# SmartHomePLC_Licenta_V2sch.net
KiCad netlist of a schematic drawn in EAGLE
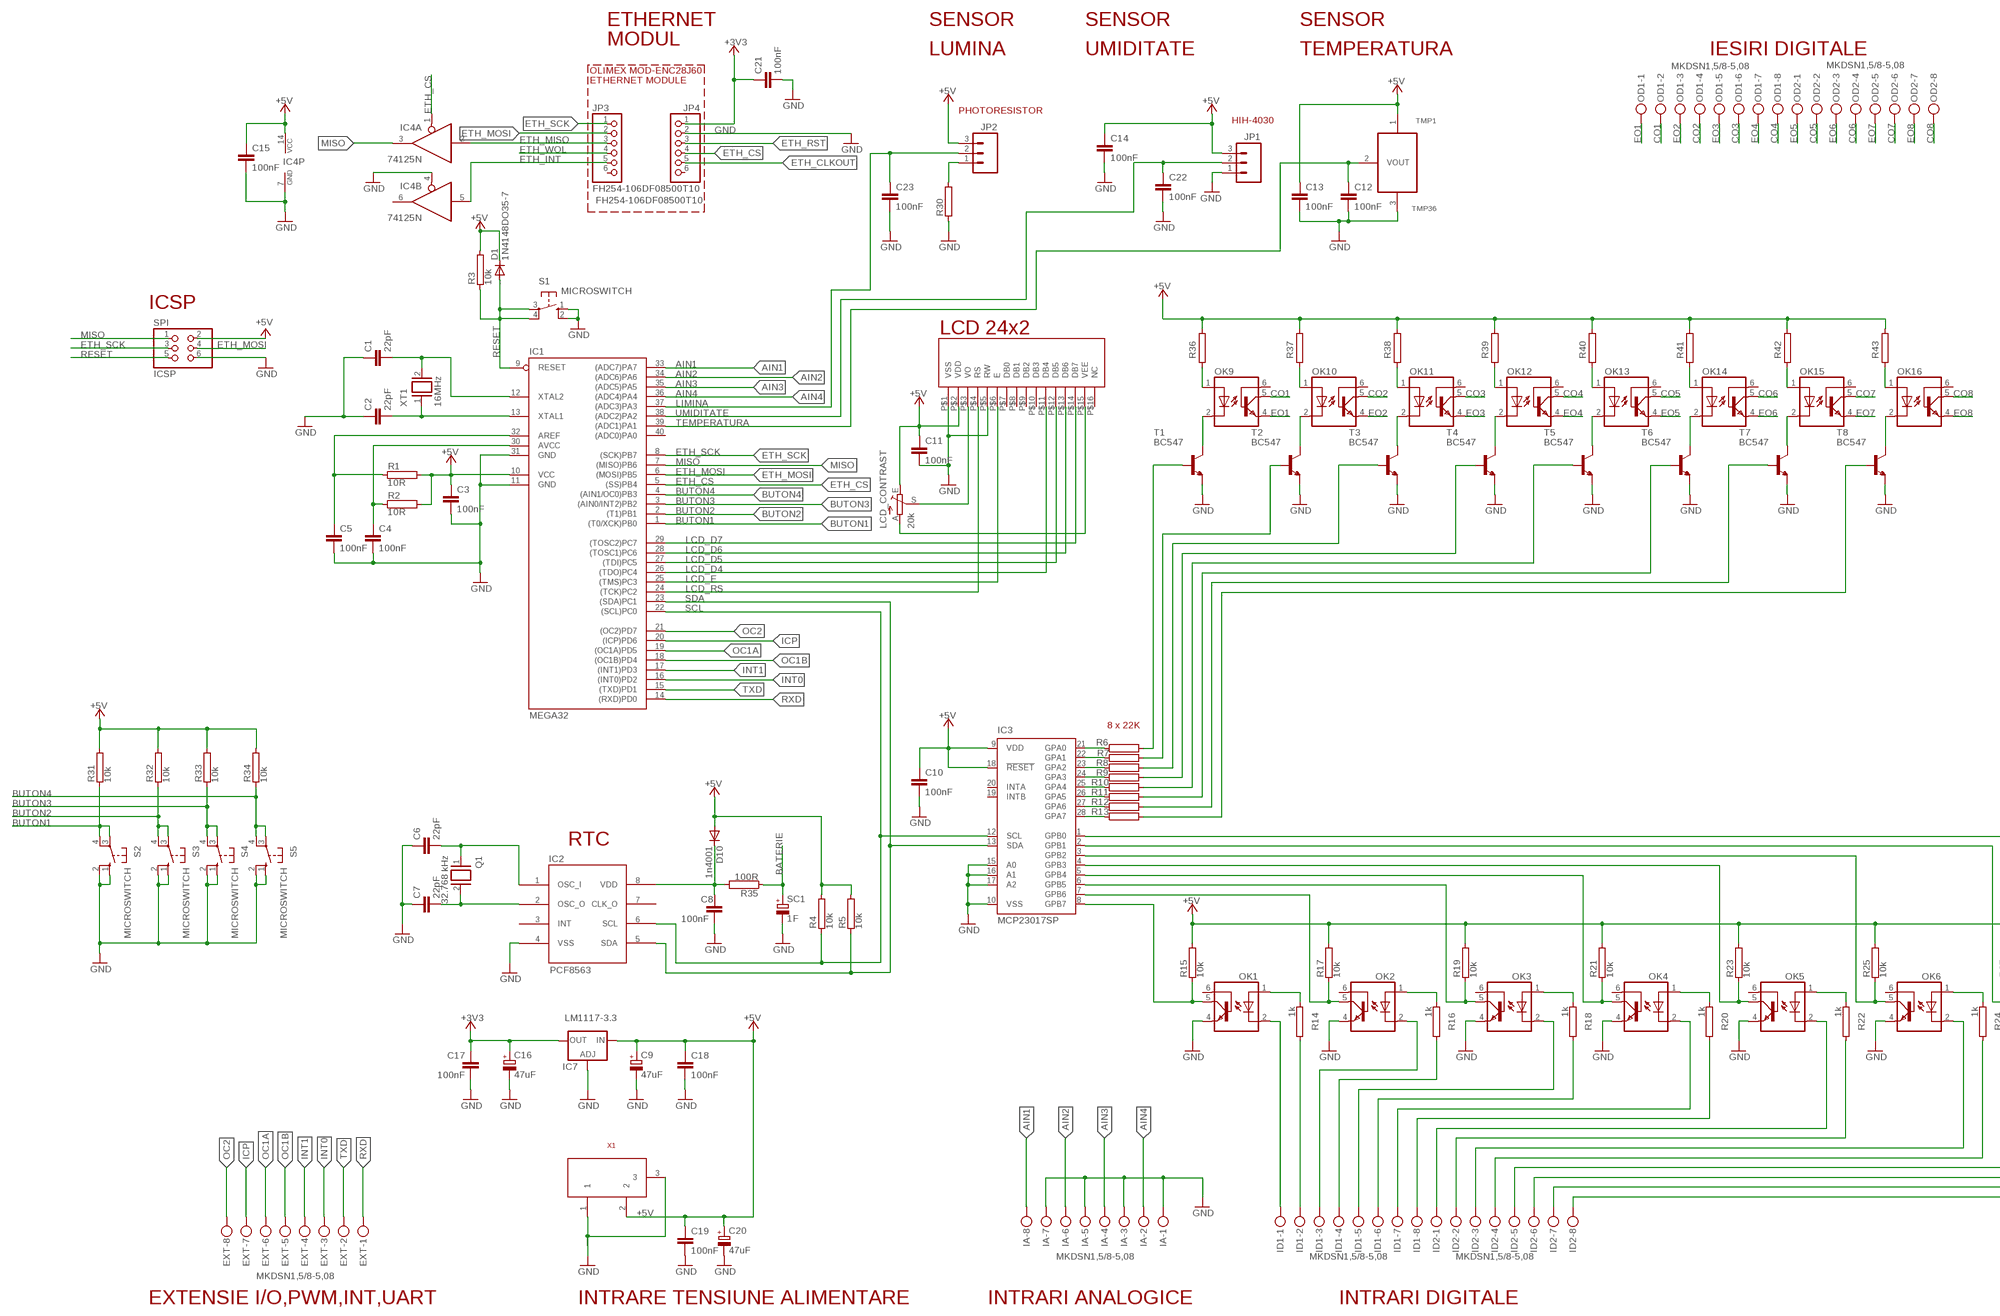
[diagram p0: schematic, sheet 1, part 1 of 2]
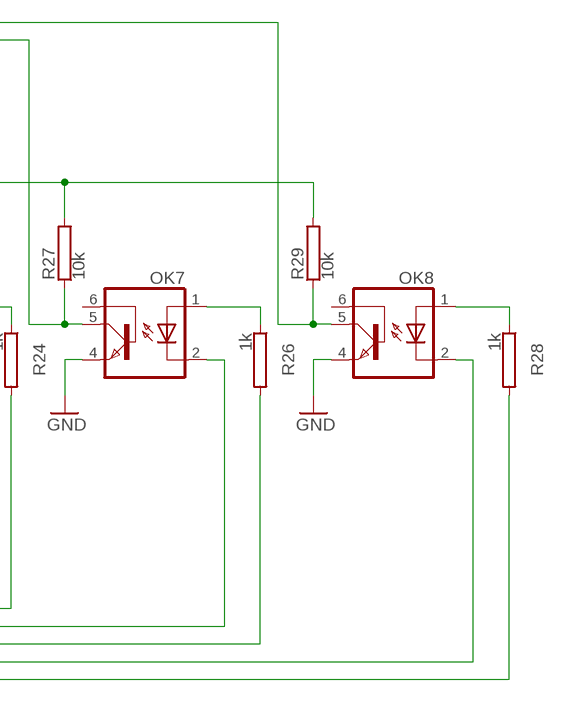
[diagram p1: schematic, sheet 1, part 2 of 2]

(export (version "E")
  (design (tool "Eeschema 10.0.6"))
  (components
    (comp (ref "C1")
      (value "22pF")
      (footprint "eagle-import:C2.5-2")
      (libsource (lib "eagle-import") (part "CAPACIOTRS2.5/2"))
    )
    (comp (ref "C2")
      (value "22pF")
      (footprint "eagle-import:C2.5-2")
      (libsource (lib "eagle-import") (part "CAPACIOTRS2.5/2"))
    )
    (comp (ref "C3")
      (value "100nF")
      (footprint "eagle-import:C5B2.5")
      (libsource (lib "eagle-import") (part "CAPACIOTRS5/2.5"))
    )
    (comp (ref "C4")
      (value "100nF")
      (footprint "eagle-import:C5B2.5")
      (libsource (lib "eagle-import") (part "CAPACIOTRS5/2.5"))
    )
    (comp (ref "C5")
      (value "100nF")
      (footprint "eagle-import:C5B2.5")
      (libsource (lib "eagle-import") (part "CAPACIOTRS5/2.5"))
    )
    (comp (ref "C6")
      (value "22pF")
      (footprint "eagle-import:C2.5-2")
      (libsource (lib "eagle-import") (part "CAPACIOTRS2.5/2"))
    )
    (comp (ref "C7")
      (value "22pF")
      (footprint "eagle-import:C2.5-2")
      (libsource (lib "eagle-import") (part "CAPACIOTRS2.5/2"))
    )
    (comp (ref "C8")
      (value "100nF")
      (footprint "eagle-import:C5B2.5")
      (libsource (lib "eagle-import") (part "CAPACIOTRS5/2.5"))
    )
    (comp (ref "C9")
      (value "47uF")
      (footprint "eagle-import:E3,5-8")
      (libsource (lib "eagle-import") (part "CAPACITORS_POLE3.5-8"))
    )
    (comp (ref "C10")
      (value "100nF")
      (footprint "eagle-import:C5B2.5")
      (libsource (lib "eagle-import") (part "CAPACIOTRS5/2.5"))
    )
    (comp (ref "C11")
      (value "100nF")
      (footprint "eagle-import:C5B2.5")
      (libsource (lib "eagle-import") (part "CAPACIOTRS5/2.5"))
    )
    (comp (ref "C12")
      (value "100nF")
      (footprint "eagle-import:C5B2.5")
      (libsource (lib "eagle-import") (part "CAPACIOTRS5/2.5"))
    )
    (comp (ref "C13")
      (value "100nF")
      (footprint "eagle-import:C5B2.5")
      (libsource (lib "eagle-import") (part "CAPACIOTRS5/2.5"))
    )
    (comp (ref "C14")
      (value "100nF")
      (footprint "eagle-import:C5B2.5")
      (libsource (lib "eagle-import") (part "CAPACIOTRS5/2.5"))
    )
    (comp (ref "C15")
      (value "100nF")
      (footprint "eagle-import:C5B2.5")
      (libsource (lib "eagle-import") (part "CAPACIOTRS5/2.5"))
    )
    (comp (ref "C16")
      (value "47uF")
      (footprint "eagle-import:E3,5-8")
      (libsource (lib "eagle-import") (part "CAPACITORS_POLE3.5-8"))
    )
    (comp (ref "C17")
      (value "100nF")
      (footprint "eagle-import:C5B2.5")
      (libsource (lib "eagle-import") (part "CAPACIOTRS5/2.5"))
    )
    (comp (ref "C18")
      (value "100nF")
      (footprint "eagle-import:C5B2.5")
      (libsource (lib "eagle-import") (part "CAPACIOTRS5/2.5"))
    )
    (comp (ref "C19")
      (value "100nF")
      (footprint "eagle-import:C5B2.5")
      (libsource (lib "eagle-import") (part "CAPACIOTRS5/2.5"))
    )
    (comp (ref "C20")
      (value "47uF")
      (footprint "eagle-import:E3,5-8")
      (libsource (lib "eagle-import") (part "CAPACITORS_POLE3.5-8"))
    )
    (comp (ref "C21")
      (value "100nF")
      (footprint "eagle-import:C5B2.5")
      (libsource (lib "eagle-import") (part "CAPACIOTRS5/2.5"))
    )
    (comp (ref "C22")
      (value "100nF")
      (footprint "eagle-import:C5B2.5")
      (libsource (lib "eagle-import") (part "CAPACIOTRS5/2.5"))
    )
    (comp (ref "C23")
      (value "100nF")
      (footprint "eagle-import:C5B2.5")
      (libsource (lib "eagle-import") (part "CAPACIOTRS5/2.5"))
    )
    (comp (ref "D1")
      (value "1N4148DO35-7")
      (footprint "eagle-import:DO35-7")
      (libsource (lib "eagle-import") (part "1N4148DO35-7"))
    )
    (comp (ref "D10")
      (value "1n4001")
      (footprint "eagle-import:DO35-10")
      (libsource (lib "eagle-import") (part "1N4148DO35-10"))
    )
    (comp (ref "EXT")
      (value "MKDSN1,5/8-5,08")
      (footprint "eagle-import:MKDSN1,5_8-5,08")
      (libsource (lib "eagle-import") (part "MKDSN1,5/8-5,08"))
    )
    (comp (ref "IA")
      (value "MKDSN1,5/8-5,08")
      (footprint "eagle-import:MKDSN1,5_8-5,08")
      (libsource (lib "eagle-import") (part "MKDSN1,5/8-5,08"))
    )
    (comp (ref "IC1")
      (value "MEGA32")
      (footprint "eagle-import:DIL40")
      (libsource (lib "eagle-import") (part "MEGA16-P"))
    )
    (comp (ref "IC2")
      (value "PCF8563P")
      (footprint "eagle-import:DIL08")
      (libsource (lib "eagle-import") (part "PCF8563P"))
    )
    (comp (ref "IC3")
      (value "MCP23017SP")
      (footprint "eagle-import:DIL28-3")
      (libsource (lib "eagle-import") (part "MCP23017SP"))
    )
    (comp (ref "IC4")
      (value "74125N")
      (footprint "eagle-import:DIL14")
      (libsource (lib "eagle-import") (part "74125N"))
    )
    (comp (ref "IC7")
      (value "LM1117-3.3")
      (footprint "eagle-import:317TS")
      (libsource (lib "eagle-import") (part "LM1117-3.3"))
    )
    (comp (ref "ID1")
      (value "MKDSN1,5/8-5,08")
      (footprint "eagle-import:MKDSN1,5_8-5,08")
      (libsource (lib "eagle-import") (part "MKDSN1,5/8-5,08"))
    )
    (comp (ref "ID2")
      (value "MKDSN1,5/8-5,08")
      (footprint "eagle-import:MKDSN1,5_8-5,08")
      (libsource (lib "eagle-import") (part "MKDSN1,5/8-5,08"))
    )
    (comp (ref "JP1")
      (value "M03LONGPADS")
      (footprint "eagle-import:1X03_LONGPADS")
      (libsource (lib "eagle-import") (part "M03LONGPADS"))
    )
    (comp (ref "JP2")
      (value "M03LONGPADS")
      (footprint "eagle-import:1X03_LONGPADS")
      (libsource (lib "eagle-import") (part "M03LONGPADS"))
    )
    (comp (ref "JP3")
      (value "FH254-106DF08500T10")
      (footprint "eagle-import:1X06")
      (libsource (lib "eagle-import") (part "6X1_F_H8,5_P2,54_STD"))
    )
    (comp (ref "JP4")
      (value "FH254-106DF08500T10")
      (footprint "eagle-import:1X06")
      (libsource (lib "eagle-import") (part "6X1_F_H8,5_P2,54_STD"))
    )
    (comp (ref "LCD_CONTRAST")
      (value "20k")
      (footprint "eagle-import:CA6V")
      (libsource (lib "eagle-import") (part "TRIM_EU-CA6V"))
    )
    (comp (ref "OD1")
      (value "MKDSN1,5/8-5,08")
      (footprint "eagle-import:MKDSN1,5_8-5,08")
      (libsource (lib "eagle-import") (part "MKDSN1,5/8-5,08"))
    )
    (comp (ref "OD2")
      (value "MKDSN1,5/8-5,08")
      (footprint "eagle-import:MKDSN1,5_8-5,08")
      (libsource (lib "eagle-import") (part "MKDSN1,5/8-5,08"))
    )
    (comp (ref "OK1")
      (value "4N35")
      (footprint "eagle-import:DIL06")
      (libsource (lib "eagle-import") (part "4N35"))
    )
    (comp (ref "OK2")
      (value "4N35")
      (footprint "eagle-import:DIL06")
      (libsource (lib "eagle-import") (part "4N35"))
    )
    (comp (ref "OK3")
      (value "4N35")
      (footprint "eagle-import:DIL06")
      (libsource (lib "eagle-import") (part "4N35"))
    )
    (comp (ref "OK4")
      (value "4N35")
      (footprint "eagle-import:DIL06")
      (libsource (lib "eagle-import") (part "4N35"))
    )
    (comp (ref "OK5")
      (value "4N35")
      (footprint "eagle-import:DIL06")
      (libsource (lib "eagle-import") (part "4N35"))
    )
    (comp (ref "OK6")
      (value "4N35")
      (footprint "eagle-import:DIL06")
      (libsource (lib "eagle-import") (part "4N35"))
    )
    (comp (ref "OK7")
      (value "4N35")
      (footprint "eagle-import:DIL06")
      (libsource (lib "eagle-import") (part "4N35"))
    )
    (comp (ref "OK8")
      (value "4N35")
      (footprint "eagle-import:DIL06")
      (libsource (lib "eagle-import") (part "4N35"))
    )
    (comp (ref "OK9")
      (value "4N35")
      (footprint "eagle-import:DIL06")
      (libsource (lib "eagle-import") (part "4N35"))
    )
    (comp (ref "OK10")
      (value "4N35")
      (footprint "eagle-import:DIL06")
      (libsource (lib "eagle-import") (part "4N35"))
    )
    (comp (ref "OK11")
      (value "4N35")
      (footprint "eagle-import:DIL06")
      (libsource (lib "eagle-import") (part "4N35"))
    )
    (comp (ref "OK12")
      (value "4N35")
      (footprint "eagle-import:DIL06")
      (libsource (lib "eagle-import") (part "4N35"))
    )
    (comp (ref "OK13")
      (value "4N35")
      (footprint "eagle-import:DIL06")
      (libsource (lib "eagle-import") (part "4N35"))
    )
    (comp (ref "OK14")
      (value "4N35")
      (footprint "eagle-import:DIL06")
      (libsource (lib "eagle-import") (part "4N35"))
    )
    (comp (ref "OK15")
      (value "4N35")
      (footprint "eagle-import:DIL06")
      (libsource (lib "eagle-import") (part "4N35"))
    )
    (comp (ref "OK16")
      (value "4N35")
      (footprint "eagle-import:DIL06")
      (libsource (lib "eagle-import") (part "4N35"))
    )
    (comp (ref "Q1")
      (value "32.768 kHz")
      (footprint "eagle-import:QS")
      (libsource (lib "eagle-import") (part "CRYSTAL_THT"))
    )
    (comp (ref "R1")
      (value "10R")
      (footprint "eagle-import:RS1_8")
      (libsource (lib "eagle-import") (part "REZISTORSRS1/8"))
    )
    (comp (ref "R2")
      (value "10R")
      (footprint "eagle-import:RS1_8")
      (libsource (lib "eagle-import") (part "REZISTORSRS1/8"))
    )
    (comp (ref "R3")
      (value "10k")
      (footprint "eagle-import:RS1_8")
      (libsource (lib "eagle-import") (part "REZISTORSRS1/8"))
    )
    (comp (ref "R4")
      (value "10k")
      (footprint "eagle-import:RS1_8")
      (libsource (lib "eagle-import") (part "REZISTORSRS1/8"))
    )
    (comp (ref "R5")
      (value "10k")
      (footprint "eagle-import:RS1_8")
      (libsource (lib "eagle-import") (part "REZISTORSRS1/8"))
    )
    (comp (ref "R6")
      (value "REZISTORSRS1/8")
      (footprint "eagle-import:RS1_8")
      (libsource (lib "eagle-import") (part "REZISTORSRS1/8"))
    )
    (comp (ref "R7")
      (value "REZISTORSRS1/8")
      (footprint "eagle-import:RS1_8")
      (libsource (lib "eagle-import") (part "REZISTORSRS1/8"))
    )
    (comp (ref "R8")
      (value "REZISTORSRS1/8")
      (footprint "eagle-import:RS1_8")
      (libsource (lib "eagle-import") (part "REZISTORSRS1/8"))
    )
    (comp (ref "R9")
      (value "REZISTORSRS1/8")
      (footprint "eagle-import:RS1_8")
      (libsource (lib "eagle-import") (part "REZISTORSRS1/8"))
    )
    (comp (ref "R10")
      (value "REZISTORSRS1/8")
      (footprint "eagle-import:RS1_8")
      (libsource (lib "eagle-import") (part "REZISTORSRS1/8"))
    )
    (comp (ref "R11")
      (value "REZISTORSRS1/8")
      (footprint "eagle-import:RS1_8")
      (libsource (lib "eagle-import") (part "REZISTORSRS1/8"))
    )
    (comp (ref "R12")
      (value "REZISTORSRS1/8")
      (footprint "eagle-import:RS1_8")
      (libsource (lib "eagle-import") (part "REZISTORSRS1/8"))
    )
    (comp (ref "R13")
      (value "REZISTORSRS1/8")
      (footprint "eagle-import:RS1_8")
      (libsource (lib "eagle-import") (part "REZISTORSRS1/8"))
    )
    (comp (ref "R14")
      (value "1k")
      (footprint "eagle-import:RS1_8")
      (libsource (lib "eagle-import") (part "REZISTORSRS1/8"))
    )
    (comp (ref "R15")
      (value "10k")
      (footprint "eagle-import:RS1_8")
      (libsource (lib "eagle-import") (part "REZISTORSRS1/8"))
    )
    (comp (ref "R16")
      (value "1k")
      (footprint "eagle-import:RS1_8")
      (libsource (lib "eagle-import") (part "REZISTORSRS1/8"))
    )
    (comp (ref "R17")
      (value "10k")
      (footprint "eagle-import:RS1_8")
      (libsource (lib "eagle-import") (part "REZISTORSRS1/8"))
    )
    (comp (ref "R18")
      (value "1k")
      (footprint "eagle-import:RS1_8")
      (libsource (lib "eagle-import") (part "REZISTORSRS1/8"))
    )
    (comp (ref "R19")
      (value "10k")
      (footprint "eagle-import:RS1_8")
      (libsource (lib "eagle-import") (part "REZISTORSRS1/8"))
    )
    (comp (ref "R20")
      (value "1k")
      (footprint "eagle-import:RS1_8")
      (libsource (lib "eagle-import") (part "REZISTORSRS1/8"))
    )
    (comp (ref "R21")
      (value "10k")
      (footprint "eagle-import:RS1_8")
      (libsource (lib "eagle-import") (part "REZISTORSRS1/8"))
    )
    (comp (ref "R22")
      (value "1k")
      (footprint "eagle-import:RS1_8")
      (libsource (lib "eagle-import") (part "REZISTORSRS1/8"))
    )
    (comp (ref "R23")
      (value "10k")
      (footprint "eagle-import:RS1_8")
      (libsource (lib "eagle-import") (part "REZISTORSRS1/8"))
    )
    (comp (ref "R24")
      (value "1k")
      (footprint "eagle-import:RS1_8")
      (libsource (lib "eagle-import") (part "REZISTORSRS1/8"))
    )
    (comp (ref "R25")
      (value "10k")
      (footprint "eagle-import:RS1_8")
      (libsource (lib "eagle-import") (part "REZISTORSRS1/8"))
    )
    (comp (ref "R26")
      (value "1k")
      (footprint "eagle-import:RS1_8")
      (libsource (lib "eagle-import") (part "REZISTORSRS1/8"))
    )
    (comp (ref "R27")
      (value "10k")
      (footprint "eagle-import:RS1_8")
      (libsource (lib "eagle-import") (part "REZISTORSRS1/8"))
    )
    (comp (ref "R28")
      (value "1k")
      (footprint "eagle-import:RS1_8")
      (libsource (lib "eagle-import") (part "REZISTORSRS1/8"))
    )
    (comp (ref "R29")
      (value "10k")
      (footprint "eagle-import:RS1_8")
      (libsource (lib "eagle-import") (part "REZISTORSRS1/8"))
    )
    (comp (ref "R30")
      (value "REZISTORSRS1/8")
      (footprint "eagle-import:RS1_8")
      (libsource (lib "eagle-import") (part "REZISTORSRS1/8"))
    )
    (comp (ref "R31")
      (value "10k")
      (footprint "eagle-import:RS1_8")
      (libsource (lib "eagle-import") (part "REZISTORSRS1/8"))
    )
    (comp (ref "R32")
      (value "10k")
      (footprint "eagle-import:RS1_8")
      (libsource (lib "eagle-import") (part "REZISTORSRS1/8"))
    )
    (comp (ref "R33")
      (value "10k")
      (footprint "eagle-import:RS1_8")
      (libsource (lib "eagle-import") (part "REZISTORSRS1/8"))
    )
    (comp (ref "R34")
      (value "10k")
      (footprint "eagle-import:RS1_8")
      (libsource (lib "eagle-import") (part "REZISTORSRS1/8"))
    )
    (comp (ref "R35")
      (value "100R")
      (footprint "eagle-import:RS1_8")
      (libsource (lib "eagle-import") (part "REZISTORSRS1/8"))
    )
    (comp (ref "R36")
      (value "REZISTORSRS1/8")
      (footprint "eagle-import:RS1_8")
      (libsource (lib "eagle-import") (part "REZISTORSRS1/8"))
    )
    (comp (ref "R37")
      (value "REZISTORSRS1/8")
      (footprint "eagle-import:RS1_8")
      (libsource (lib "eagle-import") (part "REZISTORSRS1/8"))
    )
    (comp (ref "R38")
      (value "REZISTORSRS1/8")
      (footprint "eagle-import:RS1_8")
      (libsource (lib "eagle-import") (part "REZISTORSRS1/8"))
    )
    (comp (ref "R39")
      (value "REZISTORSRS1/8")
      (footprint "eagle-import:RS1_8")
      (libsource (lib "eagle-import") (part "REZISTORSRS1/8"))
    )
    (comp (ref "R40")
      (value "REZISTORSRS1/8")
      (footprint "eagle-import:RS1_8")
      (libsource (lib "eagle-import") (part "REZISTORSRS1/8"))
    )
    (comp (ref "R41")
      (value "REZISTORSRS1/8")
      (footprint "eagle-import:RS1_8")
      (libsource (lib "eagle-import") (part "REZISTORSRS1/8"))
    )
    (comp (ref "R42")
      (value "REZISTORSRS1/8")
      (footprint "eagle-import:RS1_8")
      (libsource (lib "eagle-import") (part "REZISTORSRS1/8"))
    )
    (comp (ref "R43")
      (value "REZISTORSRS1/8")
      (footprint "eagle-import:RS1_8")
      (libsource (lib "eagle-import") (part "REZISTORSRS1/8"))
    )
    (comp (ref "S1")
      (value "MICROSWITCH")
      (footprint "eagle-import:B3F-10XX")
      (libsource (lib "eagle-import") (part "MICROSWITCH"))
    )
    (comp (ref "S2")
      (value "MICROSWITCH")
      (footprint "eagle-import:B3F-10XX")
      (libsource (lib "eagle-import") (part "MICROSWITCH"))
    )
    (comp (ref "S3")
      (value "MICROSWITCH")
      (footprint "eagle-import:B3F-10XX")
      (libsource (lib "eagle-import") (part "MICROSWITCH"))
    )
    (comp (ref "S4")
      (value "MICROSWITCH")
      (footprint "eagle-import:B3F-10XX")
      (libsource (lib "eagle-import") (part "MICROSWITCH"))
    )
    (comp (ref "S5")
      (value "MICROSWITCH")
      (footprint "eagle-import:B3F-10XX")
      (libsource (lib "eagle-import") (part "MICROSWITCH"))
    )
    (comp (ref "SC1")
      (value "1F")
      (footprint "eagle-import:DYNACAP-DB_1_3")
      (libsource (lib "eagle-import") (part "1F_SUPERCAPACITOR"))
    )
    (comp (ref "SPI")
      (value "ICSP")
      (footprint "eagle-import:2X03")
      (libsource (lib "eagle-import") (part "3X2_V_H8,5_P2,54"))
    )
    (comp (ref "T1")
      (value "BC547")
      (footprint "eagle-import:BC-TO92")
      (libsource (lib "eagle-import") (part "BC547"))
    )
    (comp (ref "T2")
      (value "BC547")
      (footprint "eagle-import:BC-TO92")
      (libsource (lib "eagle-import") (part "BC547"))
    )
    (comp (ref "T3")
      (value "BC547")
      (footprint "eagle-import:BC-TO92")
      (libsource (lib "eagle-import") (part "BC547"))
    )
    (comp (ref "T4")
      (value "BC547")
      (footprint "eagle-import:BC-TO92")
      (libsource (lib "eagle-import") (part "BC547"))
    )
    (comp (ref "T5")
      (value "BC547")
      (footprint "eagle-import:BC-TO92")
      (libsource (lib "eagle-import") (part "BC547"))
    )
    (comp (ref "T6")
      (value "BC547")
      (footprint "eagle-import:BC-TO92")
      (libsource (lib "eagle-import") (part "BC547"))
    )
    (comp (ref "T7")
      (value "BC547")
      (footprint "eagle-import:BC-TO92")
      (libsource (lib "eagle-import") (part "BC547"))
    )
    (comp (ref "T8")
      (value "BC547")
      (footprint "eagle-import:BC-TO92")
      (libsource (lib "eagle-import") (part "BC547"))
    )
    (comp (ref "TMP1")
      (value "TMP36")
      (footprint "eagle-import:BC-TO92")
      (libsource (lib "eagle-import") (part "TMP36"))
    )
    (comp (ref "U1")
      (value "LCD_RC2402")
      (footprint "eagle-import:LCD_RC2402")
      (libsource (lib "eagle-import") (part "LCD_RC2402"))
    )
    (comp (ref "X1")
      (value "0018_19746-POWER-SUPPLY")
      (footprint "eagle-import:POWERSUPPLY_DC-21MM")
      (fields (field (name "PART_NUMBER") "19746"))
      (libsource (lib "eagle-import") (part "0018_19746-POWER-SUPPLY"))
    )
    (comp (ref "XT1")
      (value "16MHz")
      (footprint "eagle-import:QS")
      (libsource (lib "eagle-import") (part "CRYSTAL_THT"))
    )
  )
  (nets
    (net (code "1") (name "+3V3") (class "Default")
      (node (ref "C16") (pin "+") (pinfunction "+_+") (pintype "passive"))
      (node (ref "C17") (pin "1") (pinfunction "1_1") (pintype "passive"))
      (node (ref "C21") (pin "1") (pinfunction "1_1") (pintype "passive"))
      (node (ref "IC7") (pin "2") (pinfunction "OUT_2") (pintype "passive"))
      (node (ref "JP4") (pin "1") (pinfunction "1_1") (pintype "passive"))
    )
    (net (code "2") (name "+5V") (class "Default")
      (node (ref "C10") (pin "1") (pinfunction "1_1") (pintype "passive"))
      (node (ref "C11") (pin "1") (pinfunction "1_1") (pintype "passive"))
      (node (ref "C13") (pin "1") (pinfunction "1_1") (pintype "passive"))
      (node (ref "C14") (pin "1") (pinfunction "1_1") (pintype "passive"))
      (node (ref "C15") (pin "1") (pinfunction "1_1") (pintype "passive"))
      (node (ref "C18") (pin "1") (pinfunction "1_1") (pintype "passive"))
      (node (ref "C19") (pin "1") (pinfunction "1_1") (pintype "passive"))
      (node (ref "C20") (pin "+") (pinfunction "+_+") (pintype "passive"))
      (node (ref "C3") (pin "1") (pinfunction "1_1") (pintype "passive"))
      (node (ref "C9") (pin "+") (pinfunction "+_+") (pintype "passive"))
      (node (ref "D1") (pin "C") (pinfunction "C_C") (pintype "passive"))
      (node (ref "D10") (pin "A") (pinfunction "A_A") (pintype "passive"))
      (node (ref "IC1") (pin "10") (pinfunction "VCC_10") (pintype "power_in"))
      (node (ref "IC3") (pin "18") (pinfunction "~{RESET}_18") (pintype "input"))
      (node (ref "IC3") (pin "9") (pinfunction "VDD_9") (pintype "power_in"))
      (node (ref "IC4") (pin "14") (pinfunction "VCC_14") (pintype "power_in"))
      (node (ref "IC7") (pin "3") (pinfunction "IN_3") (pintype "input"))
      (node (ref "JP1") (pin "3") (pinfunction "3_3") (pintype "passive"))
      (node (ref "JP2") (pin "3") (pinfunction "3_3") (pintype "passive"))
      (node (ref "LCD_CONTRAST") (pin "E") (pinfunction "E_E") (pintype "passive"))
      (node (ref "R1") (pin "2") (pinfunction "2_2") (pintype "passive"))
      (node (ref "R15") (pin "2") (pinfunction "2_2") (pintype "passive"))
      (node (ref "R17") (pin "2") (pinfunction "2_2") (pintype "passive"))
      (node (ref "R19") (pin "2") (pinfunction "2_2") (pintype "passive"))
      (node (ref "R2") (pin "2") (pinfunction "2_2") (pintype "passive"))
      (node (ref "R21") (pin "2") (pinfunction "2_2") (pintype "passive"))
      (node (ref "R23") (pin "2") (pinfunction "2_2") (pintype "passive"))
      (node (ref "R25") (pin "2") (pinfunction "2_2") (pintype "passive"))
      (node (ref "R27") (pin "2") (pinfunction "2_2") (pintype "passive"))
      (node (ref "R29") (pin "2") (pinfunction "2_2") (pintype "passive"))
      (node (ref "R3") (pin "2") (pinfunction "2_2") (pintype "passive"))
      (node (ref "R31") (pin "2") (pinfunction "2_2") (pintype "passive"))
      (node (ref "R32") (pin "2") (pinfunction "2_2") (pintype "passive"))
      (node (ref "R33") (pin "2") (pinfunction "2_2") (pintype "passive"))
      (node (ref "R34") (pin "2") (pinfunction "2_2") (pintype "passive"))
      (node (ref "R36") (pin "2") (pinfunction "2_2") (pintype "passive"))
      (node (ref "R37") (pin "2") (pinfunction "2_2") (pintype "passive"))
      (node (ref "R38") (pin "2") (pinfunction "2_2") (pintype "passive"))
      (node (ref "R39") (pin "2") (pinfunction "2_2") (pintype "passive"))
      (node (ref "R4") (pin "2") (pinfunction "2_2") (pintype "passive"))
      (node (ref "R40") (pin "2") (pinfunction "2_2") (pintype "passive"))
      (node (ref "R41") (pin "2") (pinfunction "2_2") (pintype "passive"))
      (node (ref "R42") (pin "2") (pinfunction "2_2") (pintype "passive"))
      (node (ref "R43") (pin "2") (pinfunction "2_2") (pintype "passive"))
      (node (ref "R5") (pin "2") (pinfunction "2_2") (pintype "passive"))
      (node (ref "SPI") (pin "2") (pinfunction "2_2") (pintype "passive"))
      (node (ref "TMP1") (pin "1") (pinfunction "+VS_1") (pintype "power_in"))
      (node (ref "U1") (pin "P$2") (pinfunction "VDD_P$2") (pintype "bidirectional"))
      (node (ref "X1") (pin "2") (pinfunction "2_2") (pintype "power_in"))
    )
    (net (code "3") (name "/BATERIE") (class "Default")
      (node (ref "R35") (pin "1") (pinfunction "1_1") (pintype "passive"))
      (node (ref "SC1") (pin "+") (pinfunction "+_+") (pintype "passive"))
    )
    (net (code "4") (name "/CO1") (class "Default")
      (node (ref "OD1") (pin "2") (pinfunction "KL_2") (pintype "passive"))
      (node (ref "OK9") (pin "5") (pinfunction "COL_5") (pintype "passive"))
    )
    (net (code "5") (name "/CO2") (class "Default")
      (node (ref "OD1") (pin "4") (pinfunction "KL_4") (pintype "passive"))
      (node (ref "OK10") (pin "5") (pinfunction "COL_5") (pintype "passive"))
    )
    (net (code "6") (name "/CO3") (class "Default")
      (node (ref "OD1") (pin "6") (pinfunction "KL_6") (pintype "passive"))
      (node (ref "OK11") (pin "5") (pinfunction "COL_5") (pintype "passive"))
    )
    (net (code "7") (name "/CO4") (class "Default")
      (node (ref "OD1") (pin "8") (pinfunction "KL_8") (pintype "passive"))
      (node (ref "OK12") (pin "5") (pinfunction "COL_5") (pintype "passive"))
    )
    (net (code "8") (name "/CO5") (class "Default")
      (node (ref "OD2") (pin "2") (pinfunction "KL_2") (pintype "passive"))
      (node (ref "OK13") (pin "5") (pinfunction "COL_5") (pintype "passive"))
    )
    (net (code "9") (name "/CO6") (class "Default")
      (node (ref "OD2") (pin "4") (pinfunction "KL_4") (pintype "passive"))
      (node (ref "OK14") (pin "5") (pinfunction "COL_5") (pintype "passive"))
    )
    (net (code "10") (name "/CO7") (class "Default")
      (node (ref "OD2") (pin "6") (pinfunction "KL_6") (pintype "passive"))
      (node (ref "OK15") (pin "5") (pinfunction "COL_5") (pintype "passive"))
    )
    (net (code "11") (name "/CO8") (class "Default")
      (node (ref "OD2") (pin "8") (pinfunction "KL_8") (pintype "passive"))
      (node (ref "OK16") (pin "5") (pinfunction "COL_5") (pintype "passive"))
    )
    (net (code "12") (name "/EO1") (class "Default")
      (node (ref "OD1") (pin "1") (pinfunction "KL_1") (pintype "passive"))
      (node (ref "OK9") (pin "4") (pinfunction "EMI_4") (pintype "passive"))
    )
    (net (code "13") (name "/EO2") (class "Default")
      (node (ref "OD1") (pin "3") (pinfunction "KL_3") (pintype "passive"))
      (node (ref "OK10") (pin "4") (pinfunction "EMI_4") (pintype "passive"))
    )
    (net (code "14") (name "/EO3") (class "Default")
      (node (ref "OD1") (pin "5") (pinfunction "KL_5") (pintype "passive"))
      (node (ref "OK11") (pin "4") (pinfunction "EMI_4") (pintype "passive"))
    )
    (net (code "15") (name "/EO4") (class "Default")
      (node (ref "OD1") (pin "7") (pinfunction "KL_7") (pintype "passive"))
      (node (ref "OK12") (pin "4") (pinfunction "EMI_4") (pintype "passive"))
    )
    (net (code "16") (name "/EO5") (class "Default")
      (node (ref "OD2") (pin "1") (pinfunction "KL_1") (pintype "passive"))
      (node (ref "OK13") (pin "4") (pinfunction "EMI_4") (pintype "passive"))
    )
    (net (code "17") (name "/EO6") (class "Default")
      (node (ref "OD2") (pin "3") (pinfunction "KL_3") (pintype "passive"))
      (node (ref "OK14") (pin "4") (pinfunction "EMI_4") (pintype "passive"))
    )
    (net (code "18") (name "/EO7") (class "Default")
      (node (ref "OD2") (pin "5") (pinfunction "KL_5") (pintype "passive"))
      (node (ref "OK15") (pin "4") (pinfunction "EMI_4") (pintype "passive"))
    )
    (net (code "19") (name "/EO8") (class "Default")
      (node (ref "OD2") (pin "7") (pinfunction "KL_7") (pintype "passive"))
      (node (ref "OK16") (pin "4") (pinfunction "EMI_4") (pintype "passive"))
    )
    (net (code "20") (name "/ETH_INT") (class "Default")
      (node (ref "IC4") (pin "5") (pinfunction "I_5") (pintype "input"))
      (node (ref "JP3") (pin "5") (pinfunction "5_5") (pintype "passive"))
    )
    (net (code "21") (name "/ETH_MISO") (class "Default")
      (node (ref "IC4") (pin "2") (pinfunction "I_2") (pintype "input"))
      (node (ref "JP3") (pin "3") (pinfunction "3_3") (pintype "passive"))
    )
    (net (code "22") (name "/ETH_WOL") (class "Default")
      (node (ref "JP3") (pin "4") (pinfunction "4_4") (pintype "passive"))
    )
    (net (code "23") (name "/LCD_D4") (class "Default")
      (node (ref "IC1") (pin "26") (pinfunction "(TDO)PC4_26") (pintype "bidirectional"))
      (node (ref "U1") (pin "P$11") (pinfunction "DB4_P$11") (pintype "bidirectional"))
    )
    (net (code "24") (name "/LCD_D5") (class "Default")
      (node (ref "IC1") (pin "27") (pinfunction "(TDI)PC5_27") (pintype "bidirectional"))
      (node (ref "U1") (pin "P$12") (pinfunction "DB5_P$12") (pintype "bidirectional"))
    )
    (net (code "25") (name "/LCD_D6") (class "Default")
      (node (ref "IC1") (pin "28") (pinfunction "(TOSC1)PC6_28") (pintype "bidirectional"))
      (node (ref "U1") (pin "P$13") (pinfunction "DB6_P$13") (pintype "bidirectional"))
    )
    (net (code "26") (name "/LCD_D7") (class "Default")
      (node (ref "IC1") (pin "29") (pinfunction "(TOSC2)PC7_29") (pintype "bidirectional"))
      (node (ref "U1") (pin "P$14") (pinfunction "DB7_P$14") (pintype "bidirectional"))
    )
    (net (code "27") (name "/LCD_E") (class "Default")
      (node (ref "IC1") (pin "25") (pinfunction "(TMS)PC3_25") (pintype "bidirectional"))
      (node (ref "U1") (pin "P$6") (pinfunction "E_P$6") (pintype "bidirectional"))
    )
    (net (code "28") (name "/LCD_RS") (class "Default")
      (node (ref "IC1") (pin "24") (pinfunction "(TCK)PC2_24") (pintype "bidirectional"))
      (node (ref "U1") (pin "P$4") (pinfunction "RS_P$4") (pintype "bidirectional"))
    )
    (net (code "29") (name "/LIMINA") (class "Default")
      (node (ref "C23") (pin "1") (pinfunction "1_1") (pintype "passive"))
      (node (ref "IC1") (pin "37") (pinfunction "(ADC3)PA3_37") (pintype "bidirectional"))
      (node (ref "JP2") (pin "2") (pinfunction "2_2") (pintype "passive"))
    )
    (net (code "30") (name "/RESET") (class "Default")
      (node (ref "D1") (pin "A") (pinfunction "A_A") (pintype "passive"))
      (node (ref "IC1") (pin "9") (pinfunction "RESET_9") (pintype "input"))
      (node (ref "R3") (pin "1") (pinfunction "1_1") (pintype "passive"))
      (node (ref "S1") (pin "3") (pinfunction "P_3") (pintype "passive"))
      (node (ref "S1") (pin "4") (pinfunction "P1_4") (pintype "passive"))
      (node (ref "SPI") (pin "5") (pinfunction "5_5") (pintype "passive"))
    )
    (net (code "31") (name "/SCL") (class "Default")
      (node (ref "IC1") (pin "22") (pinfunction "(SCL)PC0_22") (pintype "bidirectional"))
      (node (ref "IC2") (pin "6") (pinfunction "SCL_6") (pintype "bidirectional"))
      (node (ref "IC3") (pin "12") (pinfunction "SCL_12") (pintype "input"))
      (node (ref "R4") (pin "1") (pinfunction "1_1") (pintype "passive"))
    )
    (net (code "32") (name "/SDA") (class "Default")
      (node (ref "IC1") (pin "23") (pinfunction "(SDA)PC1_23") (pintype "bidirectional"))
      (node (ref "IC2") (pin "5") (pinfunction "SDA_5") (pintype "bidirectional"))
      (node (ref "IC3") (pin "13") (pinfunction "SDA_13") (pintype "bidirectional"))
      (node (ref "R5") (pin "1") (pinfunction "1_1") (pintype "passive"))
    )
    (net (code "33") (name "/TEMPERATURA") (class "Default")
      (node (ref "C12") (pin "1") (pinfunction "1_1") (pintype "passive"))
      (node (ref "IC1") (pin "39") (pinfunction "(ADC1)PA1_39") (pintype "bidirectional"))
      (node (ref "TMP1") (pin "2") (pinfunction "VOUT_2") (pintype "output"))
    )
    (net (code "34") (name "/UMIDITATE") (class "Default")
      (node (ref "C22") (pin "1") (pinfunction "1_1") (pintype "passive"))
      (node (ref "IC1") (pin "38") (pinfunction "(ADC2)PA2_38") (pintype "bidirectional"))
      (node (ref "JP1") (pin "2") (pinfunction "2_2") (pintype "passive"))
    )
    (net (code "35") (name "AIN1") (class "Default")
      (node (ref "IA") (pin "8") (pinfunction "KL_8") (pintype "passive"))
      (node (ref "IC1") (pin "33") (pinfunction "(ADC7)PA7_33") (pintype "bidirectional"))
    )
    (net (code "36") (name "AIN2") (class "Default")
      (node (ref "IA") (pin "6") (pinfunction "KL_6") (pintype "passive"))
      (node (ref "IC1") (pin "34") (pinfunction "(ADC6)PA6_34") (pintype "bidirectional"))
    )
    (net (code "37") (name "AIN3") (class "Default")
      (node (ref "IA") (pin "4") (pinfunction "KL_4") (pintype "passive"))
      (node (ref "IC1") (pin "35") (pinfunction "(ADC5)PA5_35") (pintype "bidirectional"))
    )
    (net (code "38") (name "AIN4") (class "Default")
      (node (ref "IA") (pin "2") (pinfunction "KL_2") (pintype "passive"))
      (node (ref "IC1") (pin "36") (pinfunction "(ADC4)PA4_36") (pintype "bidirectional"))
    )
    (net (code "39") (name "BUTON1") (class "Default")
      (node (ref "IC1") (pin "1") (pinfunction "(T0/XCK)PB0_1") (pintype "bidirectional"))
      (node (ref "R31") (pin "1") (pinfunction "1_1") (pintype "passive"))
      (node (ref "S2") (pin "3") (pinfunction "P_3") (pintype "passive"))
      (node (ref "S2") (pin "4") (pinfunction "P1_4") (pintype "passive"))
    )
    (net (code "40") (name "BUTON2") (class "Default")
      (node (ref "IC1") (pin "2") (pinfunction "(T1)PB1_2") (pintype "bidirectional"))
      (node (ref "R32") (pin "1") (pinfunction "1_1") (pintype "passive"))
      (node (ref "S3") (pin "3") (pinfunction "P_3") (pintype "passive"))
      (node (ref "S3") (pin "4") (pinfunction "P1_4") (pintype "passive"))
    )
    (net (code "41") (name "BUTON3") (class "Default")
      (node (ref "IC1") (pin "3") (pinfunction "(AIN0/INT2)PB2_3") (pintype "bidirectional"))
      (node (ref "R33") (pin "1") (pinfunction "1_1") (pintype "passive"))
      (node (ref "S4") (pin "3") (pinfunction "P_3") (pintype "passive"))
      (node (ref "S4") (pin "4") (pinfunction "P1_4") (pintype "passive"))
    )
    (net (code "42") (name "BUTON4") (class "Default")
      (node (ref "IC1") (pin "4") (pinfunction "(AIN1/OC0)PB3_4") (pintype "bidirectional"))
      (node (ref "R34") (pin "1") (pinfunction "1_1") (pintype "passive"))
      (node (ref "S5") (pin "3") (pinfunction "P_3") (pintype "passive"))
      (node (ref "S5") (pin "4") (pinfunction "P1_4") (pintype "passive"))
    )
    (net (code "43") (name "ETH_CLKOUT") (class "Default")
      (node (ref "JP4") (pin "5") (pinfunction "5_5") (pintype "passive"))
    )
    (net (code "44") (name "ETH_CS") (class "Default")
      (node (ref "IC1") (pin "5") (pinfunction "(SS)PB4_5") (pintype "bidirectional"))
      (node (ref "IC4") (pin "1") (pinfunction "OE_1") (pintype "input"))
      (node (ref "JP4") (pin "4") (pinfunction "4_4") (pintype "passive"))
    )
    (net (code "45") (name "ETH_MOSI") (class "Default")
      (node (ref "IC1") (pin "6") (pinfunction "(MOSI)PB5_6") (pintype "bidirectional"))
      (node (ref "JP3") (pin "2") (pinfunction "2_2") (pintype "passive"))
      (node (ref "SPI") (pin "4") (pinfunction "4_4") (pintype "passive"))
    )
    (net (code "46") (name "ETH_RST") (class "Default")
      (node (ref "JP4") (pin "3") (pinfunction "3_3") (pintype "passive"))
    )
    (net (code "47") (name "ETH_SCK") (class "Default")
      (node (ref "IC1") (pin "8") (pinfunction "(SCK)PB7_8") (pintype "bidirectional"))
      (node (ref "JP3") (pin "1") (pinfunction "1_1") (pintype "passive"))
      (node (ref "SPI") (pin "3") (pinfunction "3_3") (pintype "passive"))
    )
    (net (code "48") (name "GND") (class "Default")
      (node (ref "C1") (pin "1") (pinfunction "1_1") (pintype "passive"))
      (node (ref "C10") (pin "2") (pinfunction "2_2") (pintype "passive"))
      (node (ref "C11") (pin "2") (pinfunction "2_2") (pintype "passive"))
      (node (ref "C12") (pin "2") (pinfunction "2_2") (pintype "passive"))
      (node (ref "C13") (pin "2") (pinfunction "2_2") (pintype "passive"))
      (node (ref "C14") (pin "2") (pinfunction "2_2") (pintype "passive"))
      (node (ref "C15") (pin "2") (pinfunction "2_2") (pintype "passive"))
      (node (ref "C16") (pin "-") (pinfunction "-_-") (pintype "passive"))
      (node (ref "C17") (pin "2") (pinfunction "2_2") (pintype "passive"))
      (node (ref "C18") (pin "2") (pinfunction "2_2") (pintype "passive"))
      (node (ref "C19") (pin "2") (pinfunction "2_2") (pintype "passive"))
      (node (ref "C2") (pin "1") (pinfunction "1_1") (pintype "passive"))
      (node (ref "C20") (pin "-") (pinfunction "-_-") (pintype "passive"))
      (node (ref "C21") (pin "2") (pinfunction "2_2") (pintype "passive"))
      (node (ref "C22") (pin "2") (pinfunction "2_2") (pintype "passive"))
      (node (ref "C23") (pin "2") (pinfunction "2_2") (pintype "passive"))
      (node (ref "C3") (pin "2") (pinfunction "2_2") (pintype "passive"))
      (node (ref "C4") (pin "2") (pinfunction "2_2") (pintype "passive"))
      (node (ref "C5") (pin "2") (pinfunction "2_2") (pintype "passive"))
      (node (ref "C6") (pin "1") (pinfunction "1_1") (pintype "passive"))
      (node (ref "C7") (pin "1") (pinfunction "1_1") (pintype "passive"))
      (node (ref "C8") (pin "2") (pinfunction "2_2") (pintype "passive"))
      (node (ref "C9") (pin "-") (pinfunction "-_-") (pintype "passive"))
      (node (ref "IA") (pin "1") (pinfunction "KL_1") (pintype "passive"))
      (node (ref "IA") (pin "3") (pinfunction "KL_3") (pintype "passive"))
      (node (ref "IA") (pin "5") (pinfunction "KL_5") (pintype "passive"))
      (node (ref "IA") (pin "7") (pinfunction "KL_7") (pintype "passive"))
      (node (ref "IC1") (pin "11") (pinfunction "GND_11") (pintype "power_in"))
      (node (ref "IC1") (pin "31") (pinfunction "GND_31") (pintype "power_in"))
      (node (ref "IC2") (pin "4") (pinfunction "VSS_4") (pintype "bidirectional"))
      (node (ref "IC3") (pin "10") (pinfunction "VSS_10") (pintype "power_in"))
      (node (ref "IC3") (pin "15") (pinfunction "A0_15") (pintype "input"))
      (node (ref "IC3") (pin "16") (pinfunction "A1_16") (pintype "input"))
      (node (ref "IC3") (pin "17") (pinfunction "A2_17") (pintype "input"))
      (node (ref "IC4") (pin "4") (pinfunction "OE_4") (pintype "input"))
      (node (ref "IC4") (pin "7") (pinfunction "GND_7") (pintype "power_in"))
      (node (ref "IC7") (pin "1") (pinfunction "ADJ_1") (pintype "input"))
      (node (ref "JP1") (pin "1") (pinfunction "1_1") (pintype "passive"))
      (node (ref "JP4") (pin "2") (pinfunction "2_2") (pintype "passive"))
      (node (ref "OK1") (pin "4") (pinfunction "EMI_4") (pintype "passive"))
      (node (ref "OK2") (pin "4") (pinfunction "EMI_4") (pintype "passive"))
      (node (ref "OK3") (pin "4") (pinfunction "EMI_4") (pintype "passive"))
      (node (ref "OK4") (pin "4") (pinfunction "EMI_4") (pintype "passive"))
      (node (ref "OK5") (pin "4") (pinfunction "EMI_4") (pintype "passive"))
      (node (ref "OK6") (pin "4") (pinfunction "EMI_4") (pintype "passive"))
      (node (ref "OK7") (pin "4") (pinfunction "EMI_4") (pintype "passive"))
      (node (ref "OK8") (pin "4") (pinfunction "EMI_4") (pintype "passive"))
      (node (ref "R30") (pin "1") (pinfunction "1_1") (pintype "passive"))
      (node (ref "S1") (pin "1") (pinfunction "S_1") (pintype "passive"))
      (node (ref "S1") (pin "2") (pinfunction "S1_2") (pintype "passive"))
      (node (ref "S2") (pin "1") (pinfunction "S_1") (pintype "passive"))
      (node (ref "S2") (pin "2") (pinfunction "S1_2") (pintype "passive"))
      (node (ref "S3") (pin "1") (pinfunction "S_1") (pintype "passive"))
      (node (ref "S3") (pin "2") (pinfunction "S1_2") (pintype "passive"))
      (node (ref "S4") (pin "1") (pinfunction "S_1") (pintype "passive"))
      (node (ref "S4") (pin "2") (pinfunction "S1_2") (pintype "passive"))
      (node (ref "S5") (pin "1") (pinfunction "S_1") (pintype "passive"))
      (node (ref "S5") (pin "2") (pinfunction "S1_2") (pintype "passive"))
      (node (ref "SC1") (pin "-") (pinfunction "-_-") (pintype "passive"))
      (node (ref "SPI") (pin "6") (pinfunction "6_6") (pintype "passive"))
      (node (ref "T1") (pin "1") (pinfunction "E_1") (pintype "passive"))
      (node (ref "T2") (pin "1") (pinfunction "E_1") (pintype "passive"))
      (node (ref "T3") (pin "1") (pinfunction "E_1") (pintype "passive"))
      (node (ref "T4") (pin "1") (pinfunction "E_1") (pintype "passive"))
      (node (ref "T5") (pin "1") (pinfunction "E_1") (pintype "passive"))
      (node (ref "T6") (pin "1") (pinfunction "E_1") (pintype "passive"))
      (node (ref "T7") (pin "1") (pinfunction "E_1") (pintype "passive"))
      (node (ref "T8") (pin "1") (pinfunction "E_1") (pintype "passive"))
      (node (ref "TMP1") (pin "3") (pinfunction "GND_3") (pintype "power_in"))
      (node (ref "U1") (pin "P$1") (pinfunction "VSS_P$1") (pintype "bidirectional"))
      (node (ref "U1") (pin "P$5") (pinfunction "RW_P$5") (pintype "bidirectional"))
      (node (ref "X1") (pin "1") (pinfunction "1_1") (pintype "power_in"))
      (node (ref "X1") (pin "3") (pinfunction "3_3") (pintype "power_in"))
    )
    (net (code "49") (name "ICP") (class "Default")
      (node (ref "EXT") (pin "7") (pinfunction "KL_7") (pintype "passive"))
      (node (ref "IC1") (pin "20") (pinfunction "(ICP)PD6_20") (pintype "bidirectional"))
    )
    (net (code "50") (name "INT0") (class "Default")
      (node (ref "EXT") (pin "3") (pinfunction "KL_3") (pintype "passive"))
      (node (ref "IC1") (pin "16") (pinfunction "(INT0)PD2_16") (pintype "bidirectional"))
    )
    (net (code "51") (name "INT1") (class "Default")
      (node (ref "EXT") (pin "4") (pinfunction "KL_4") (pintype "passive"))
      (node (ref "IC1") (pin "17") (pinfunction "(INT1)PD3_17") (pintype "bidirectional"))
    )
    (net (code "52") (name "MISO") (class "Default")
      (node (ref "IC1") (pin "7") (pinfunction "(MISO)PB6_7") (pintype "bidirectional"))
      (node (ref "IC4") (pin "3") (pinfunction "O_3") (pintype "tri_state"))
      (node (ref "SPI") (pin "1") (pinfunction "1_1") (pintype "passive"))
    )
    (net (code "53") (name "Net-(IC1-AREF)") (class "Default")
      (node (ref "C5") (pin "1") (pinfunction "1_1") (pintype "passive"))
      (node (ref "IC1") (pin "32") (pinfunction "AREF_32") (pintype "passive"))
      (node (ref "R1") (pin "1") (pinfunction "1_1") (pintype "passive"))
    )
    (net (code "54") (name "Net-(IC1-AVCC)") (class "Default")
      (node (ref "C4") (pin "1") (pinfunction "1_1") (pintype "passive"))
      (node (ref "IC1") (pin "30") (pinfunction "AVCC_30") (pintype "power_in"))
      (node (ref "R2") (pin "1") (pinfunction "1_1") (pintype "passive"))
    )
    (net (code "55") (name "Net-(IC1-XTAL1)") (class "Default")
      (node (ref "C2") (pin "2") (pinfunction "2_2") (pintype "passive"))
      (node (ref "IC1") (pin "13") (pinfunction "XTAL1_13") (pintype "bidirectional"))
      (node (ref "XT1") (pin "1") (pinfunction "1_1") (pintype "passive"))
    )
    (net (code "56") (name "Net-(IC1-XTAL2)") (class "Default")
      (node (ref "C1") (pin "2") (pinfunction "2_2") (pintype "passive"))
      (node (ref "IC1") (pin "12") (pinfunction "XTAL2_12") (pintype "bidirectional"))
      (node (ref "XT1") (pin "2") (pinfunction "2_2") (pintype "passive"))
    )
    (net (code "57") (name "Net-(IC2-OSC_I)") (class "Default")
      (node (ref "C6") (pin "2") (pinfunction "2_2") (pintype "passive"))
      (node (ref "IC2") (pin "1") (pinfunction "OSC_I_1") (pintype "bidirectional"))
      (node (ref "Q1") (pin "1") (pinfunction "1_1") (pintype "passive"))
    )
    (net (code "58") (name "Net-(IC2-OSC_O)") (class "Default")
      (node (ref "C7") (pin "2") (pinfunction "2_2") (pintype "passive"))
      (node (ref "IC2") (pin "2") (pinfunction "OSC_O_2") (pintype "bidirectional"))
      (node (ref "Q1") (pin "2") (pinfunction "2_2") (pintype "passive"))
    )
    (net (code "59") (name "Net-(IC2-VDD)") (class "Default")
      (node (ref "C8") (pin "1") (pinfunction "1_1") (pintype "passive"))
      (node (ref "D10") (pin "C") (pinfunction "C_C") (pintype "passive"))
      (node (ref "IC2") (pin "8") (pinfunction "VDD_8") (pintype "bidirectional"))
      (node (ref "R35") (pin "2") (pinfunction "2_2") (pintype "passive"))
    )
    (net (code "60") (name "Net-(IC3-GPA0)") (class "Default")
      (node (ref "IC3") (pin "21") (pinfunction "GPA0_21") (pintype "bidirectional"))
      (node (ref "R6") (pin "1") (pinfunction "1_1") (pintype "passive"))
    )
    (net (code "61") (name "Net-(IC3-GPA1)") (class "Default")
      (node (ref "IC3") (pin "22") (pinfunction "GPA1_22") (pintype "bidirectional"))
      (node (ref "R7") (pin "1") (pinfunction "1_1") (pintype "passive"))
    )
    (net (code "62") (name "Net-(IC3-GPA2)") (class "Default")
      (node (ref "IC3") (pin "23") (pinfunction "GPA2_23") (pintype "bidirectional"))
      (node (ref "R8") (pin "1") (pinfunction "1_1") (pintype "passive"))
    )
    (net (code "63") (name "Net-(IC3-GPA3)") (class "Default")
      (node (ref "IC3") (pin "24") (pinfunction "GPA3_24") (pintype "bidirectional"))
      (node (ref "R9") (pin "1") (pinfunction "1_1") (pintype "passive"))
    )
    (net (code "64") (name "Net-(IC3-GPA4)") (class "Default")
      (node (ref "IC3") (pin "25") (pinfunction "GPA4_25") (pintype "bidirectional"))
      (node (ref "R10") (pin "1") (pinfunction "1_1") (pintype "passive"))
    )
    (net (code "65") (name "Net-(IC3-GPA5)") (class "Default")
      (node (ref "IC3") (pin "26") (pinfunction "GPA5_26") (pintype "bidirectional"))
      (node (ref "R11") (pin "1") (pinfunction "1_1") (pintype "passive"))
    )
    (net (code "66") (name "Net-(IC3-GPA6)") (class "Default")
      (node (ref "IC3") (pin "27") (pinfunction "GPA6_27") (pintype "bidirectional"))
      (node (ref "R12") (pin "1") (pinfunction "1_1") (pintype "passive"))
    )
    (net (code "67") (name "Net-(IC3-GPA7)") (class "Default")
      (node (ref "IC3") (pin "28") (pinfunction "GPA7_28") (pintype "bidirectional"))
      (node (ref "R13") (pin "1") (pinfunction "1_1") (pintype "passive"))
    )
    (net (code "68") (name "Net-(IC3-GPB0)") (class "Default")
      (node (ref "IC3") (pin "1") (pinfunction "GPB0_1") (pintype "bidirectional"))
      (node (ref "OK8") (pin "5") (pinfunction "COL_5") (pintype "passive"))
      (node (ref "R29") (pin "1") (pinfunction "1_1") (pintype "passive"))
    )
    (net (code "69") (name "Net-(IC3-GPB1)") (class "Default")
      (node (ref "IC3") (pin "2") (pinfunction "GPB1_2") (pintype "bidirectional"))
      (node (ref "OK7") (pin "5") (pinfunction "COL_5") (pintype "passive"))
      (node (ref "R27") (pin "1") (pinfunction "1_1") (pintype "passive"))
    )
    (net (code "70") (name "Net-(IC3-GPB2)") (class "Default")
      (node (ref "IC3") (pin "3") (pinfunction "GPB2_3") (pintype "bidirectional"))
      (node (ref "OK6") (pin "5") (pinfunction "COL_5") (pintype "passive"))
      (node (ref "R25") (pin "1") (pinfunction "1_1") (pintype "passive"))
    )
    (net (code "71") (name "Net-(IC3-GPB3)") (class "Default")
      (node (ref "IC3") (pin "4") (pinfunction "GPB3_4") (pintype "bidirectional"))
      (node (ref "OK5") (pin "5") (pinfunction "COL_5") (pintype "passive"))
      (node (ref "R23") (pin "1") (pinfunction "1_1") (pintype "passive"))
    )
    (net (code "72") (name "Net-(IC3-GPB4)") (class "Default")
      (node (ref "IC3") (pin "5") (pinfunction "GPB4_5") (pintype "bidirectional"))
      (node (ref "OK4") (pin "5") (pinfunction "COL_5") (pintype "passive"))
      (node (ref "R21") (pin "1") (pinfunction "1_1") (pintype "passive"))
    )
    (net (code "73") (name "Net-(IC3-GPB5)") (class "Default")
      (node (ref "IC3") (pin "6") (pinfunction "GPB5_6") (pintype "bidirectional"))
      (node (ref "OK3") (pin "5") (pinfunction "COL_5") (pintype "passive"))
      (node (ref "R19") (pin "1") (pinfunction "1_1") (pintype "passive"))
    )
    (net (code "74") (name "Net-(IC3-GPB6)") (class "Default")
      (node (ref "IC3") (pin "7") (pinfunction "GPB6_7") (pintype "bidirectional"))
      (node (ref "OK2") (pin "5") (pinfunction "COL_5") (pintype "passive"))
      (node (ref "R17") (pin "1") (pinfunction "1_1") (pintype "passive"))
    )
    (net (code "75") (name "Net-(IC3-GPB7)") (class "Default")
      (node (ref "IC3") (pin "8") (pinfunction "GPB7_8") (pintype "bidirectional"))
      (node (ref "OK1") (pin "5") (pinfunction "COL_5") (pintype "passive"))
      (node (ref "R15") (pin "1") (pinfunction "1_1") (pintype "passive"))
    )
    (net (code "76") (name "Net-(ID1A-KL)") (class "Default")
      (node (ref "ID1") (pin "1") (pinfunction "KL_1") (pintype "passive"))
      (node (ref "OK1") (pin "2") (pinfunction "C_2") (pintype "passive"))
    )
    (net (code "77") (name "Net-(ID1B-KL)") (class "Default")
      (node (ref "ID1") (pin "2") (pinfunction "KL_2") (pintype "passive"))
      (node (ref "R14") (pin "2") (pinfunction "2_2") (pintype "passive"))
    )
    (net (code "78") (name "Net-(ID1C-KL)") (class "Default")
      (node (ref "ID1") (pin "3") (pinfunction "KL_3") (pintype "passive"))
      (node (ref "OK2") (pin "2") (pinfunction "C_2") (pintype "passive"))
    )
    (net (code "79") (name "Net-(ID1D-KL)") (class "Default")
      (node (ref "ID1") (pin "4") (pinfunction "KL_4") (pintype "passive"))
      (node (ref "R16") (pin "2") (pinfunction "2_2") (pintype "passive"))
    )
    (net (code "80") (name "Net-(ID1E-KL)") (class "Default")
      (node (ref "ID1") (pin "5") (pinfunction "KL_5") (pintype "passive"))
      (node (ref "OK3") (pin "2") (pinfunction "C_2") (pintype "passive"))
    )
    (net (code "81") (name "Net-(ID1F-KL)") (class "Default")
      (node (ref "ID1") (pin "6") (pinfunction "KL_6") (pintype "passive"))
      (node (ref "R18") (pin "2") (pinfunction "2_2") (pintype "passive"))
    )
    (net (code "82") (name "Net-(ID1G-KL)") (class "Default")
      (node (ref "ID1") (pin "7") (pinfunction "KL_7") (pintype "passive"))
      (node (ref "OK4") (pin "2") (pinfunction "C_2") (pintype "passive"))
    )
    (net (code "83") (name "Net-(ID1H-KL)") (class "Default")
      (node (ref "ID1") (pin "8") (pinfunction "KL_8") (pintype "passive"))
      (node (ref "R20") (pin "2") (pinfunction "2_2") (pintype "passive"))
    )
    (net (code "84") (name "Net-(ID2A-KL)") (class "Default")
      (node (ref "ID2") (pin "1") (pinfunction "KL_1") (pintype "passive"))
      (node (ref "OK5") (pin "2") (pinfunction "C_2") (pintype "passive"))
    )
    (net (code "85") (name "Net-(ID2B-KL)") (class "Default")
      (node (ref "ID2") (pin "2") (pinfunction "KL_2") (pintype "passive"))
      (node (ref "R22") (pin "2") (pinfunction "2_2") (pintype "passive"))
    )
    (net (code "86") (name "Net-(ID2C-KL)") (class "Default")
      (node (ref "ID2") (pin "3") (pinfunction "KL_3") (pintype "passive"))
      (node (ref "OK6") (pin "2") (pinfunction "C_2") (pintype "passive"))
    )
    (net (code "87") (name "Net-(ID2D-KL)") (class "Default")
      (node (ref "ID2") (pin "4") (pinfunction "KL_4") (pintype "passive"))
      (node (ref "R24") (pin "2") (pinfunction "2_2") (pintype "passive"))
    )
    (net (code "88") (name "Net-(ID2E-KL)") (class "Default")
      (node (ref "ID2") (pin "5") (pinfunction "KL_5") (pintype "passive"))
      (node (ref "OK7") (pin "2") (pinfunction "C_2") (pintype "passive"))
    )
    (net (code "89") (name "Net-(ID2F-KL)") (class "Default")
      (node (ref "ID2") (pin "6") (pinfunction "KL_6") (pintype "passive"))
      (node (ref "R26") (pin "2") (pinfunction "2_2") (pintype "passive"))
    )
    (net (code "90") (name "Net-(ID2G-KL)") (class "Default")
      (node (ref "ID2") (pin "7") (pinfunction "KL_7") (pintype "passive"))
      (node (ref "OK8") (pin "2") (pinfunction "C_2") (pintype "passive"))
    )
    (net (code "91") (name "Net-(ID2H-KL)") (class "Default")
      (node (ref "ID2") (pin "8") (pinfunction "KL_8") (pintype "passive"))
      (node (ref "R28") (pin "2") (pinfunction "2_2") (pintype "passive"))
    )
    (net (code "92") (name "Net-(JP2-Pad1)") (class "Default")
      (node (ref "JP2") (pin "1") (pinfunction "1_1") (pintype "passive"))
      (node (ref "R30") (pin "2") (pinfunction "2_2") (pintype "passive"))
    )
    (net (code "93") (name "Net-(OK1-A)") (class "Default")
      (node (ref "OK1") (pin "1") (pinfunction "A_1") (pintype "passive"))
      (node (ref "R14") (pin "1") (pinfunction "1_1") (pintype "passive"))
    )
    (net (code "94") (name "Net-(OK2-A)") (class "Default")
      (node (ref "OK2") (pin "1") (pinfunction "A_1") (pintype "passive"))
      (node (ref "R16") (pin "1") (pinfunction "1_1") (pintype "passive"))
    )
    (net (code "95") (name "Net-(OK3-A)") (class "Default")
      (node (ref "OK3") (pin "1") (pinfunction "A_1") (pintype "passive"))
      (node (ref "R18") (pin "1") (pinfunction "1_1") (pintype "passive"))
    )
    (net (code "96") (name "Net-(OK4-A)") (class "Default")
      (node (ref "OK4") (pin "1") (pinfunction "A_1") (pintype "passive"))
      (node (ref "R20") (pin "1") (pinfunction "1_1") (pintype "passive"))
    )
    (net (code "97") (name "Net-(OK5-A)") (class "Default")
      (node (ref "OK5") (pin "1") (pinfunction "A_1") (pintype "passive"))
      (node (ref "R22") (pin "1") (pinfunction "1_1") (pintype "passive"))
    )
    (net (code "98") (name "Net-(OK6-A)") (class "Default")
      (node (ref "OK6") (pin "1") (pinfunction "A_1") (pintype "passive"))
      (node (ref "R24") (pin "1") (pinfunction "1_1") (pintype "passive"))
    )
    (net (code "99") (name "Net-(OK7-A)") (class "Default")
      (node (ref "OK7") (pin "1") (pinfunction "A_1") (pintype "passive"))
      (node (ref "R26") (pin "1") (pinfunction "1_1") (pintype "passive"))
    )
    (net (code "100") (name "Net-(OK8-A)") (class "Default")
      (node (ref "OK8") (pin "1") (pinfunction "A_1") (pintype "passive"))
      (node (ref "R28") (pin "1") (pinfunction "1_1") (pintype "passive"))
    )
    (net (code "101") (name "Net-(OK9-A)") (class "Default")
      (node (ref "OK9") (pin "1") (pinfunction "A_1") (pintype "passive"))
      (node (ref "R36") (pin "1") (pinfunction "1_1") (pintype "passive"))
    )
    (net (code "102") (name "Net-(OK9-C)") (class "Default")
      (node (ref "OK9") (pin "2") (pinfunction "C_2") (pintype "passive"))
      (node (ref "T1") (pin "3") (pinfunction "C_3") (pintype "passive"))
    )
    (net (code "103") (name "Net-(OK10-A)") (class "Default")
      (node (ref "OK10") (pin "1") (pinfunction "A_1") (pintype "passive"))
      (node (ref "R37") (pin "1") (pinfunction "1_1") (pintype "passive"))
    )
    (net (code "104") (name "Net-(OK10-C)") (class "Default")
      (node (ref "OK10") (pin "2") (pinfunction "C_2") (pintype "passive"))
      (node (ref "T2") (pin "3") (pinfunction "C_3") (pintype "passive"))
    )
    (net (code "105") (name "Net-(OK11-A)") (class "Default")
      (node (ref "OK11") (pin "1") (pinfunction "A_1") (pintype "passive"))
      (node (ref "R38") (pin "1") (pinfunction "1_1") (pintype "passive"))
    )
    (net (code "106") (name "Net-(OK11-C)") (class "Default")
      (node (ref "OK11") (pin "2") (pinfunction "C_2") (pintype "passive"))
      (node (ref "T3") (pin "3") (pinfunction "C_3") (pintype "passive"))
    )
    (net (code "107") (name "Net-(OK12-A)") (class "Default")
      (node (ref "OK12") (pin "1") (pinfunction "A_1") (pintype "passive"))
      (node (ref "R39") (pin "1") (pinfunction "1_1") (pintype "passive"))
    )
    (net (code "108") (name "Net-(OK12-C)") (class "Default")
      (node (ref "OK12") (pin "2") (pinfunction "C_2") (pintype "passive"))
      (node (ref "T4") (pin "3") (pinfunction "C_3") (pintype "passive"))
    )
    (net (code "109") (name "Net-(OK13-A)") (class "Default")
      (node (ref "OK13") (pin "1") (pinfunction "A_1") (pintype "passive"))
      (node (ref "R40") (pin "1") (pinfunction "1_1") (pintype "passive"))
    )
    (net (code "110") (name "Net-(OK13-C)") (class "Default")
      (node (ref "OK13") (pin "2") (pinfunction "C_2") (pintype "passive"))
      (node (ref "T5") (pin "3") (pinfunction "C_3") (pintype "passive"))
    )
    (net (code "111") (name "Net-(OK14-A)") (class "Default")
      (node (ref "OK14") (pin "1") (pinfunction "A_1") (pintype "passive"))
      (node (ref "R41") (pin "1") (pinfunction "1_1") (pintype "passive"))
    )
    (net (code "112") (name "Net-(OK14-C)") (class "Default")
      (node (ref "OK14") (pin "2") (pinfunction "C_2") (pintype "passive"))
      (node (ref "T6") (pin "3") (pinfunction "C_3") (pintype "passive"))
    )
    (net (code "113") (name "Net-(OK15-A)") (class "Default")
      (node (ref "OK15") (pin "1") (pinfunction "A_1") (pintype "passive"))
      (node (ref "R42") (pin "1") (pinfunction "1_1") (pintype "passive"))
    )
    (net (code "114") (name "Net-(OK15-C)") (class "Default")
      (node (ref "OK15") (pin "2") (pinfunction "C_2") (pintype "passive"))
      (node (ref "T7") (pin "3") (pinfunction "C_3") (pintype "passive"))
    )
    (net (code "115") (name "Net-(OK16-A)") (class "Default")
      (node (ref "OK16") (pin "1") (pinfunction "A_1") (pintype "passive"))
      (node (ref "R43") (pin "1") (pinfunction "1_1") (pintype "passive"))
    )
    (net (code "116") (name "Net-(OK16-C)") (class "Default")
      (node (ref "OK16") (pin "2") (pinfunction "C_2") (pintype "passive"))
      (node (ref "T8") (pin "3") (pinfunction "C_3") (pintype "passive"))
    )
    (net (code "117") (name "Net-(T1-B)") (class "Default")
      (node (ref "R6") (pin "2") (pinfunction "2_2") (pintype "passive"))
      (node (ref "T1") (pin "2") (pinfunction "B_2") (pintype "passive"))
    )
    (net (code "118") (name "Net-(T2-B)") (class "Default")
      (node (ref "R7") (pin "2") (pinfunction "2_2") (pintype "passive"))
      (node (ref "T2") (pin "2") (pinfunction "B_2") (pintype "passive"))
    )
    (net (code "119") (name "Net-(T3-B)") (class "Default")
      (node (ref "R8") (pin "2") (pinfunction "2_2") (pintype "passive"))
      (node (ref "T3") (pin "2") (pinfunction "B_2") (pintype "passive"))
    )
    (net (code "120") (name "Net-(T4-B)") (class "Default")
      (node (ref "R9") (pin "2") (pinfunction "2_2") (pintype "passive"))
      (node (ref "T4") (pin "2") (pinfunction "B_2") (pintype "passive"))
    )
    (net (code "121") (name "Net-(T5-B)") (class "Default")
      (node (ref "R10") (pin "2") (pinfunction "2_2") (pintype "passive"))
      (node (ref "T5") (pin "2") (pinfunction "B_2") (pintype "passive"))
    )
    (net (code "122") (name "Net-(T6-B)") (class "Default")
      (node (ref "R11") (pin "2") (pinfunction "2_2") (pintype "passive"))
      (node (ref "T6") (pin "2") (pinfunction "B_2") (pintype "passive"))
    )
    (net (code "123") (name "Net-(T7-B)") (class "Default")
      (node (ref "R12") (pin "2") (pinfunction "2_2") (pintype "passive"))
      (node (ref "T7") (pin "2") (pinfunction "B_2") (pintype "passive"))
    )
    (net (code "124") (name "Net-(T8-B)") (class "Default")
      (node (ref "R13") (pin "2") (pinfunction "2_2") (pintype "passive"))
      (node (ref "T8") (pin "2") (pinfunction "B_2") (pintype "passive"))
    )
    (net (code "125") (name "Net-(U1-VEE)") (class "Default")
      (node (ref "LCD_CONTRAST") (pin "A") (pinfunction "A_A") (pintype "passive"))
      (node (ref "U1") (pin "P$15") (pinfunction "VEE_P$15") (pintype "bidirectional"))
    )
    (net (code "126") (name "Net-(U1-VO)") (class "Default")
      (node (ref "LCD_CONTRAST") (pin "S") (pinfunction "S_S") (pintype "passive"))
      (node (ref "U1") (pin "P$3") (pinfunction "VO_P$3") (pintype "bidirectional"))
    )
    (net (code "127") (name "OC1A") (class "Default")
      (node (ref "EXT") (pin "6") (pinfunction "KL_6") (pintype "passive"))
      (node (ref "IC1") (pin "19") (pinfunction "(OC1A)PD5_19") (pintype "bidirectional"))
    )
    (net (code "128") (name "OC1B") (class "Default")
      (node (ref "EXT") (pin "5") (pinfunction "KL_5") (pintype "passive"))
      (node (ref "IC1") (pin "18") (pinfunction "(OC1B)PD4_18") (pintype "bidirectional"))
    )
    (net (code "129") (name "OC2") (class "Default")
      (node (ref "EXT") (pin "8") (pinfunction "KL_8") (pintype "passive"))
      (node (ref "IC1") (pin "21") (pinfunction "(OC2)PD7_21") (pintype "bidirectional"))
    )
    (net (code "130") (name "RXD") (class "Default")
      (node (ref "EXT") (pin "1") (pinfunction "KL_1") (pintype "passive"))
      (node (ref "IC1") (pin "14") (pinfunction "(RXD)PD0_14") (pintype "bidirectional"))
    )
    (net (code "131") (name "TXD") (class "Default")
      (node (ref "EXT") (pin "2") (pinfunction "KL_2") (pintype "passive"))
      (node (ref "IC1") (pin "15") (pinfunction "(TXD)PD1_15") (pintype "bidirectional"))
    )
    (net (code "132") (name "unconnected-(IC1-(ADC0)PA0-Pad40)") (class "Default")
      (node (ref "IC1") (pin "40") (pinfunction "(ADC0)PA0_40") (pintype "bidirectional"))
    )
    (net (code "133") (name "unconnected-(IC2-CLK_O-Pad7)") (class "Default")
      (node (ref "IC2") (pin "7") (pinfunction "CLK_O_7") (pintype "bidirectional"))
    )
    (net (code "134") (name "unconnected-(IC2-INT-Pad3)") (class "Default")
      (node (ref "IC2") (pin "3") (pinfunction "INT_3") (pintype "bidirectional"))
    )
    (net (code "135") (name "unconnected-(IC3-INTA-Pad20)") (class "Default")
      (node (ref "IC3") (pin "20") (pinfunction "INTA_20") (pintype "output"))
    )
    (net (code "136") (name "unconnected-(IC3-INTB-Pad19)") (class "Default")
      (node (ref "IC3") (pin "19") (pinfunction "INTB_19") (pintype "output"))
    )
    (net (code "137") (name "unconnected-(IC4B-O-Pad6)") (class "Default")
      (node (ref "IC4") (pin "6") (pinfunction "O_6") (pintype "tri_state"))
    )
    (net (code "138") (name "unconnected-(JP3-Pad6)") (class "Default")
      (node (ref "JP3") (pin "6") (pinfunction "6_6") (pintype "passive"))
    )
    (net (code "139") (name "unconnected-(JP4-Pad6)") (class "Default")
      (node (ref "JP4") (pin "6") (pinfunction "6_6") (pintype "passive"))
    )
    (net (code "140") (name "unconnected-(OK1-BAS-Pad6)") (class "Default")
      (node (ref "OK1") (pin "6") (pinfunction "BAS_6") (pintype "passive"))
    )
    (net (code "141") (name "unconnected-(OK2-BAS-Pad6)") (class "Default")
      (node (ref "OK2") (pin "6") (pinfunction "BAS_6") (pintype "passive"))
    )
    (net (code "142") (name "unconnected-(OK3-BAS-Pad6)") (class "Default")
      (node (ref "OK3") (pin "6") (pinfunction "BAS_6") (pintype "passive"))
    )
    (net (code "143") (name "unconnected-(OK4-BAS-Pad6)") (class "Default")
      (node (ref "OK4") (pin "6") (pinfunction "BAS_6") (pintype "passive"))
    )
    (net (code "144") (name "unconnected-(OK5-BAS-Pad6)") (class "Default")
      (node (ref "OK5") (pin "6") (pinfunction "BAS_6") (pintype "passive"))
    )
    (net (code "145") (name "unconnected-(OK6-BAS-Pad6)") (class "Default")
      (node (ref "OK6") (pin "6") (pinfunction "BAS_6") (pintype "passive"))
    )
    (net (code "146") (name "unconnected-(OK7-BAS-Pad6)") (class "Default")
      (node (ref "OK7") (pin "6") (pinfunction "BAS_6") (pintype "passive"))
    )
    (net (code "147") (name "unconnected-(OK8-BAS-Pad6)") (class "Default")
      (node (ref "OK8") (pin "6") (pinfunction "BAS_6") (pintype "passive"))
    )
    (net (code "148") (name "unconnected-(OK9-BAS-Pad6)") (class "Default")
      (node (ref "OK9") (pin "6") (pinfunction "BAS_6") (pintype "passive"))
    )
    (net (code "149") (name "unconnected-(OK10-BAS-Pad6)") (class "Default")
      (node (ref "OK10") (pin "6") (pinfunction "BAS_6") (pintype "passive"))
    )
    (net (code "150") (name "unconnected-(OK11-BAS-Pad6)") (class "Default")
      (node (ref "OK11") (pin "6") (pinfunction "BAS_6") (pintype "passive"))
    )
    (net (code "151") (name "unconnected-(OK12-BAS-Pad6)") (class "Default")
      (node (ref "OK12") (pin "6") (pinfunction "BAS_6") (pintype "passive"))
    )
    (net (code "152") (name "unconnected-(OK13-BAS-Pad6)") (class "Default")
      (node (ref "OK13") (pin "6") (pinfunction "BAS_6") (pintype "passive"))
    )
    (net (code "153") (name "unconnected-(OK14-BAS-Pad6)") (class "Default")
      (node (ref "OK14") (pin "6") (pinfunction "BAS_6") (pintype "passive"))
    )
    (net (code "154") (name "unconnected-(OK15-BAS-Pad6)") (class "Default")
      (node (ref "OK15") (pin "6") (pinfunction "BAS_6") (pintype "passive"))
    )
    (net (code "155") (name "unconnected-(OK16-BAS-Pad6)") (class "Default")
      (node (ref "OK16") (pin "6") (pinfunction "BAS_6") (pintype "passive"))
    )
    (net (code "156") (name "unconnected-(U1-DB0-PadP$7)") (class "Default")
      (node (ref "U1") (pin "P$7") (pinfunction "DB0_P$7") (pintype "bidirectional"))
    )
    (net (code "157") (name "unconnected-(U1-DB1-PadP$8)") (class "Default")
      (node (ref "U1") (pin "P$8") (pinfunction "DB1_P$8") (pintype "bidirectional"))
    )
    (net (code "158") (name "unconnected-(U1-DB2-PadP$9)") (class "Default")
      (node (ref "U1") (pin "P$9") (pinfunction "DB2_P$9") (pintype "bidirectional"))
    )
    (net (code "159") (name "unconnected-(U1-DB3-PadP$10)") (class "Default")
      (node (ref "U1") (pin "P$10") (pinfunction "DB3_P$10") (pintype "bidirectional"))
    )
    (net (code "160") (name "unconnected-(U1-NC-PadP$16)") (class "Default")
      (node (ref "U1") (pin "P$16") (pinfunction "NC_P$16") (pintype "bidirectional"))
    )
  )
)
